# esenode.net
KiCad netlist of a schematic drawn in EAGLE
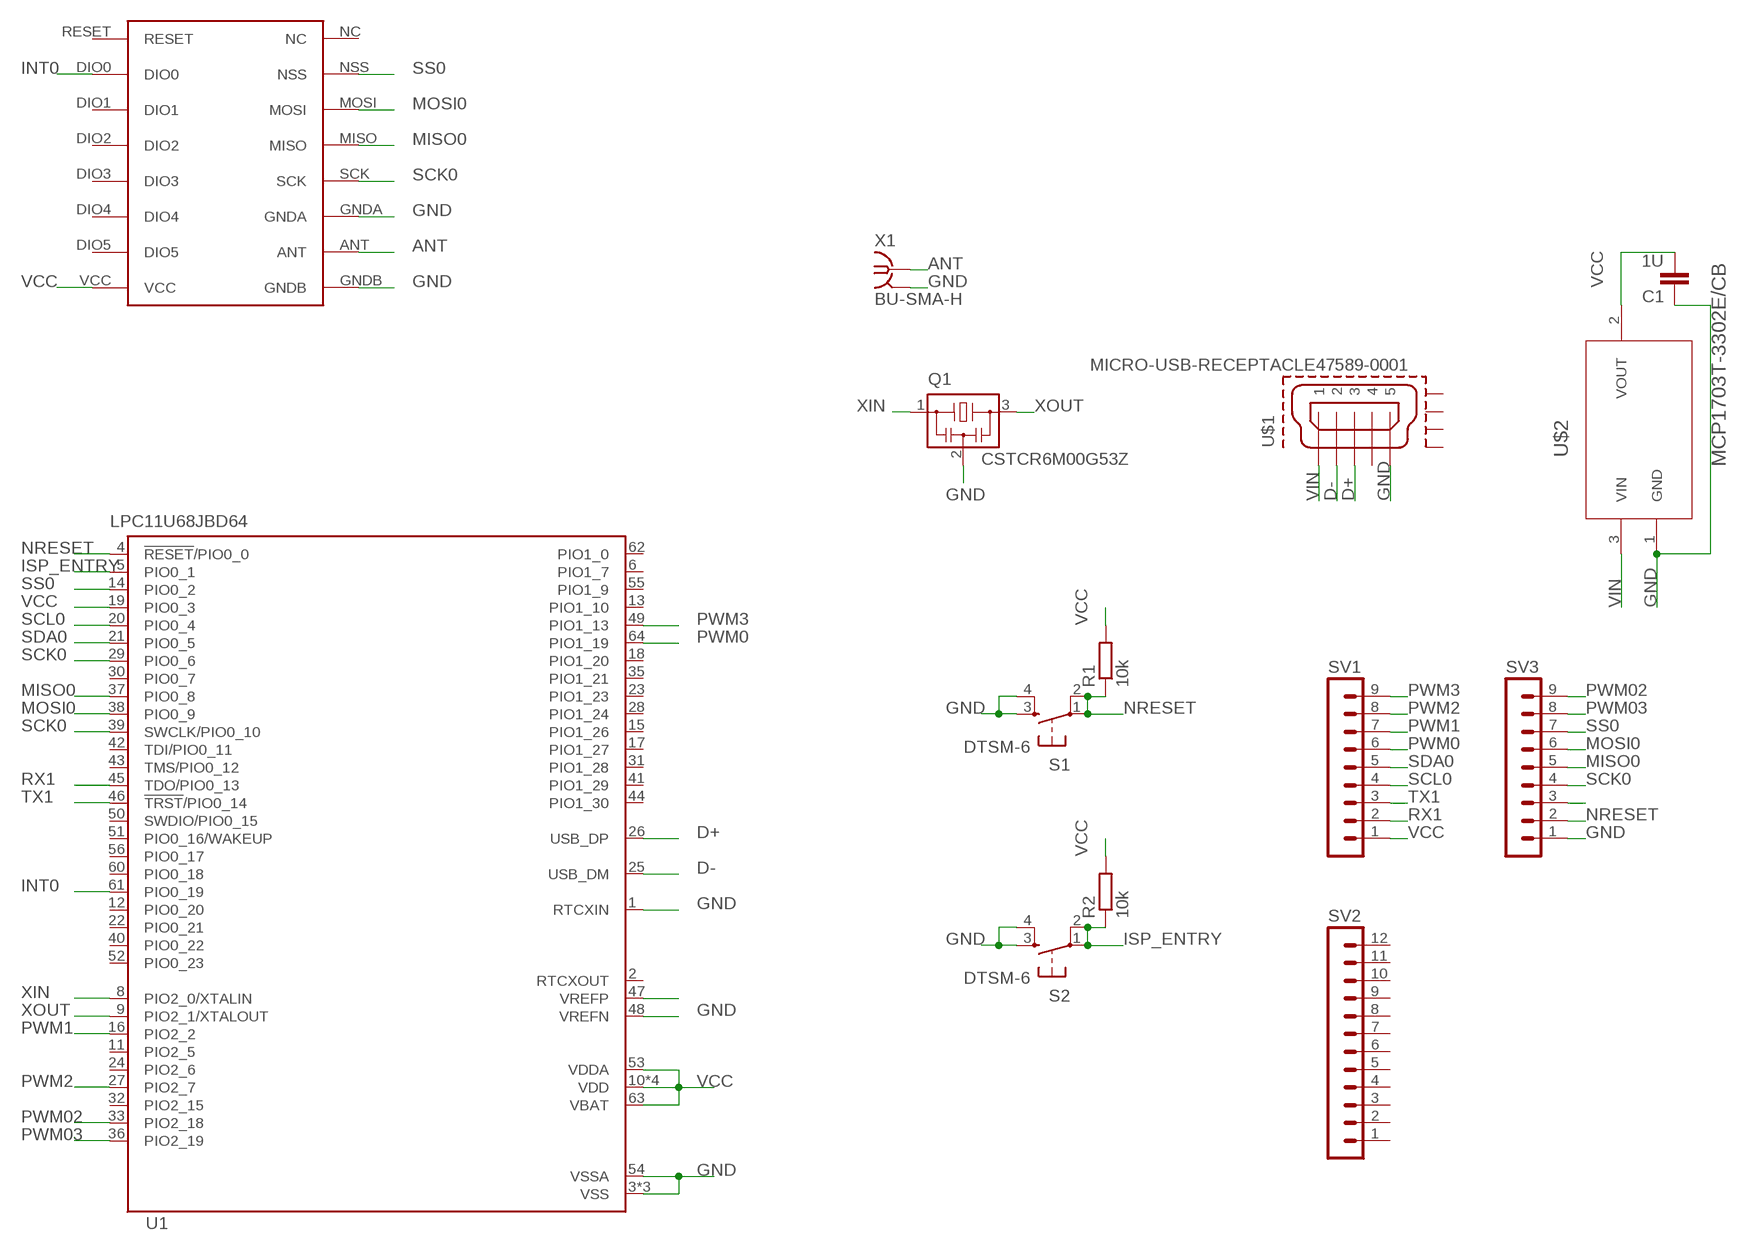
[diagram p0: schematic, sheet 1]

(export (version "E")
  (design (tool "Eeschema 10.0.6"))
  (components
    (comp (ref "C1")
      (value "1U")
      (footprint "eagle-import:C0805")
      (libsource (lib "eagle-import") (part "C-EUC0805"))
    )
    (comp (ref "Q1")
      (value "CSTCR6M00G53Z")
      (footprint "eagle-import:CSTCR6M")
      (fields (field (name "MPN") "CSTCR6M00G53-R0"))
      (libsource (lib "eagle-import") (part "CSTCR6M00G53Z"))
    )
    (comp (ref "R1")
      (value "10k")
      (footprint "eagle-import:M0805")
      (libsource (lib "eagle-import") (part "R-EU_M0805"))
    )
    (comp (ref "R2")
      (value "10k")
      (footprint "eagle-import:M0805")
      (libsource (lib "eagle-import") (part "R-EU_M0805"))
    )
    (comp (ref "S1")
      (value "DTSM-6")
      (footprint "eagle-import:DTSM-6")
      (libsource (lib "eagle-import") (part "DTSM-6"))
    )
    (comp (ref "S2")
      (value "DTSM-6")
      (footprint "eagle-import:DTSM-6")
      (libsource (lib "eagle-import") (part "DTSM-6"))
    )
    (comp (ref "SV1")
      (value "MA09-1")
      (footprint "eagle-import:MA09-1")
      (libsource (lib "eagle-import") (part "MA09-1"))
    )
    (comp (ref "SV2")
      (value "MA12-1")
      (footprint "eagle-import:MA12-1")
      (libsource (lib "eagle-import") (part "MA12-1"))
    )
    (comp (ref "SV3")
      (value "MA09-1")
      (footprint "eagle-import:MA09-1")
      (libsource (lib "eagle-import") (part "MA09-1"))
    )
    (comp (ref "U$1")
      (value "MICRO-USB-RECEPTACLE47589-0001")
      (footprint "eagle-import:47589-0001")
      (libsource (lib "eagle-import") (part "MICRO-USB-RECEPTACLE47589-0001"))
    )
    (comp (ref "U$2")
      (value "MCP1703T-3302E/CB")
      (footprint "eagle-import:SOT95P300X145-3N")
      (libsource (lib "eagle-import") (part "MCP1703T-3302E/CB"))
    )
    (comp (ref "U$3")
      (value "RFM69HW")
      (footprint "eagle-import:RFM")
      (libsource (lib "eagle-import") (part "RFM69HW"))
    )
    (comp (ref "U1")
      (value "LPC11U68JBD64")
      (footprint "eagle-import:SOT314-2")
      (libsource (lib "eagle-import") (part "LPC11U68JBD64"))
    )
    (comp (ref "X1")
      (value "BU-SMA-H")
      (footprint "eagle-import:BU-SMA-H")
      (libsource (lib "eagle-import") (part "BU-SMA-H"))
    )
  )
  (nets
    (net (code "1") (name "/ANT") (class "Default")
      (node (ref "U$3") (pin "ANT") (pinfunction "ANT_ANT") (pintype "bidirectional"))
      (node (ref "X1") (pin "1") (pinfunction "1_1") (pintype "passive"))
    )
    (net (code "2") (name "/D+") (class "Default")
      (node (ref "U$1") (pin "3") (pinfunction "3_3") (pintype "input"))
      (node (ref "U1") (pin "26") (pinfunction "USB_DP_26") (pintype "bidirectional"))
    )
    (net (code "3") (name "/D-") (class "Default")
      (node (ref "U$1") (pin "2") (pinfunction "2_2") (pintype "input"))
      (node (ref "U1") (pin "25") (pinfunction "USB_DM_25") (pintype "bidirectional"))
    )
    (net (code "4") (name "/GND") (class "Default")
      (node (ref "C1") (pin "1") (pinfunction "1_1") (pintype "passive"))
      (node (ref "Q1") (pin "2") (pinfunction "2_2") (pintype "passive"))
      (node (ref "S1") (pin "3") (pinfunction "3_3") (pintype "passive"))
      (node (ref "S1") (pin "4") (pinfunction "4_4") (pintype "passive"))
      (node (ref "S2") (pin "3") (pinfunction "3_3") (pintype "passive"))
      (node (ref "S2") (pin "4") (pinfunction "4_4") (pintype "passive"))
      (node (ref "SV3") (pin "1") (pinfunction "1_1") (pintype "passive"))
      (node (ref "U$1") (pin "5") (pinfunction "5_5") (pintype "input"))
      (node (ref "U$2") (pin "1") (pinfunction "GND_1") (pintype "passive"))
      (node (ref "U$3") (pin "GNDA") (pinfunction "GNDA_GNDA") (pintype "bidirectional"))
      (node (ref "U$3") (pin "GNDB") (pinfunction "GNDB_GNDB") (pintype "bidirectional"))
      (node (ref "U1") (pin "1") (pinfunction "RTCXIN_1") (pintype "bidirectional"))
      (node (ref "U1") (pin "3") (pinfunction "VSS_3") (pintype "bidirectional"))
      (node (ref "U1") (pin "48") (pinfunction "VREFN_48") (pintype "bidirectional"))
      (node (ref "U1") (pin "54") (pinfunction "VSSA_54") (pintype "bidirectional"))
      (node (ref "U1") (pin "57") (pinfunction "VSS_57") (pintype "bidirectional"))
      (node (ref "U1") (pin "7") (pinfunction "VSS_7") (pintype "bidirectional"))
      (node (ref "X1") (pin "2") (pinfunction "2_2") (pintype "passive"))
      (node (ref "X1") (pin "3") (pinfunction "2_3") (pintype "passive"))
      (node (ref "X1") (pin "4") (pinfunction "2_4") (pintype "passive"))
      (node (ref "X1") (pin "5") (pinfunction "2_5") (pintype "passive"))
    )
    (net (code "5") (name "/INT0") (class "Default")
      (node (ref "U$3") (pin "DIO0") (pinfunction "DIO0_DIO0") (pintype "bidirectional"))
      (node (ref "U1") (pin "61") (pinfunction "PIO0_19_61") (pintype "bidirectional"))
    )
    (net (code "6") (name "/ISP_ENTRY") (class "Default")
      (node (ref "R2") (pin "1") (pinfunction "1_1") (pintype "passive"))
      (node (ref "S2") (pin "1") (pinfunction "1_1") (pintype "passive"))
      (node (ref "S2") (pin "2") (pinfunction "2_2") (pintype "passive"))
      (node (ref "U1") (pin "5") (pinfunction "PIO0_1_5") (pintype "bidirectional"))
    )
    (net (code "7") (name "/MISO0") (class "Default")
      (node (ref "SV3") (pin "5") (pinfunction "5_5") (pintype "passive"))
      (node (ref "U$3") (pin "MISO") (pinfunction "MISO_MISO") (pintype "bidirectional"))
      (node (ref "U1") (pin "37") (pinfunction "PIO0_8_37") (pintype "bidirectional"))
    )
    (net (code "8") (name "/MOSI0") (class "Default")
      (node (ref "SV3") (pin "6") (pinfunction "6_6") (pintype "passive"))
      (node (ref "U$3") (pin "MOSI") (pinfunction "MOSI_MOSI") (pintype "bidirectional"))
      (node (ref "U1") (pin "38") (pinfunction "PIO0_9_38") (pintype "bidirectional"))
    )
    (net (code "9") (name "/NRESET") (class "Default")
      (node (ref "R1") (pin "1") (pinfunction "1_1") (pintype "passive"))
      (node (ref "S1") (pin "1") (pinfunction "1_1") (pintype "passive"))
      (node (ref "S1") (pin "2") (pinfunction "2_2") (pintype "passive"))
      (node (ref "SV3") (pin "2") (pinfunction "2_2") (pintype "passive"))
      (node (ref "U1") (pin "4") (pinfunction "~{RESET}/PIO0_0_4") (pintype "bidirectional"))
    )
    (net (code "10") (name "/PWM0") (class "Default")
      (node (ref "SV1") (pin "6") (pinfunction "6_6") (pintype "passive"))
      (node (ref "U1") (pin "64") (pinfunction "PIO1_19_64") (pintype "bidirectional"))
    )
    (net (code "11") (name "/PWM1") (class "Default")
      (node (ref "SV1") (pin "7") (pinfunction "7_7") (pintype "passive"))
      (node (ref "U1") (pin "16") (pinfunction "PIO2_2_16") (pintype "bidirectional"))
    )
    (net (code "12") (name "/PWM02") (class "Default")
      (node (ref "SV3") (pin "9") (pinfunction "9_9") (pintype "passive"))
      (node (ref "U1") (pin "33") (pinfunction "PIO2_18_33") (pintype "bidirectional"))
    )
    (net (code "13") (name "/PWM2") (class "Default")
      (node (ref "SV1") (pin "8") (pinfunction "8_8") (pintype "passive"))
      (node (ref "U1") (pin "27") (pinfunction "PIO2_7_27") (pintype "bidirectional"))
    )
    (net (code "14") (name "/PWM3") (class "Default")
      (node (ref "SV1") (pin "9") (pinfunction "9_9") (pintype "passive"))
      (node (ref "U1") (pin "49") (pinfunction "PIO1_13_49") (pintype "bidirectional"))
    )
    (net (code "15") (name "/PWM03") (class "Default")
      (node (ref "SV3") (pin "8") (pinfunction "8_8") (pintype "passive"))
      (node (ref "U1") (pin "36") (pinfunction "PIO2_19_36") (pintype "bidirectional"))
    )
    (net (code "16") (name "/RX1") (class "Default")
      (node (ref "SV1") (pin "2") (pinfunction "2_2") (pintype "passive"))
      (node (ref "U1") (pin "45") (pinfunction "TDO/PIO0_13_45") (pintype "bidirectional"))
    )
    (net (code "17") (name "/SCK0") (class "Default")
      (node (ref "SV3") (pin "4") (pinfunction "4_4") (pintype "passive"))
      (node (ref "U$3") (pin "SCK") (pinfunction "SCK_SCK") (pintype "bidirectional"))
      (node (ref "U1") (pin "29") (pinfunction "PIO0_6_29") (pintype "bidirectional"))
      (node (ref "U1") (pin "39") (pinfunction "SWCLK/PIO0_10_39") (pintype "bidirectional"))
    )
    (net (code "18") (name "/SCL0") (class "Default")
      (node (ref "SV1") (pin "4") (pinfunction "4_4") (pintype "passive"))
      (node (ref "U1") (pin "20") (pinfunction "PIO0_4_20") (pintype "bidirectional"))
    )
    (net (code "19") (name "/SDA0") (class "Default")
      (node (ref "SV1") (pin "5") (pinfunction "5_5") (pintype "passive"))
      (node (ref "U1") (pin "21") (pinfunction "PIO0_5_21") (pintype "bidirectional"))
    )
    (net (code "20") (name "/SS0") (class "Default")
      (node (ref "SV3") (pin "7") (pinfunction "7_7") (pintype "passive"))
      (node (ref "U$3") (pin "NSS") (pinfunction "NSS_NSS") (pintype "bidirectional"))
      (node (ref "U1") (pin "14") (pinfunction "PIO0_2_14") (pintype "bidirectional"))
    )
    (net (code "21") (name "/TX1") (class "Default")
      (node (ref "SV1") (pin "3") (pinfunction "3_3") (pintype "passive"))
      (node (ref "U1") (pin "46") (pinfunction "~{TRST}/PIO0_14_46") (pintype "bidirectional"))
    )
    (net (code "22") (name "/VCC") (class "Default")
      (node (ref "C1") (pin "2") (pinfunction "2_2") (pintype "passive"))
      (node (ref "R1") (pin "2") (pinfunction "2_2") (pintype "passive"))
      (node (ref "R2") (pin "2") (pinfunction "2_2") (pintype "passive"))
      (node (ref "SV1") (pin "1") (pinfunction "1_1") (pintype "passive"))
      (node (ref "U$2") (pin "2") (pinfunction "VOUT_2") (pintype "output"))
      (node (ref "U$3") (pin "VCC") (pinfunction "VCC_VCC") (pintype "bidirectional"))
      (node (ref "U1") (pin "10") (pinfunction "VDD_10") (pintype "bidirectional"))
      (node (ref "U1") (pin "19") (pinfunction "PIO0_3_19") (pintype "bidirectional"))
      (node (ref "U1") (pin "34") (pinfunction "VDD_34") (pintype "bidirectional"))
      (node (ref "U1") (pin "53") (pinfunction "VDDA_53") (pintype "bidirectional"))
      (node (ref "U1") (pin "58") (pinfunction "VDD_58") (pintype "bidirectional"))
      (node (ref "U1") (pin "59") (pinfunction "VDD_59") (pintype "bidirectional"))
      (node (ref "U1") (pin "63") (pinfunction "VBAT_63") (pintype "bidirectional"))
    )
    (net (code "23") (name "/VIN") (class "Default")
      (node (ref "U$1") (pin "1") (pinfunction "1_1") (pintype "input"))
      (node (ref "U$2") (pin "3") (pinfunction "VIN_3") (pintype "input"))
    )
    (net (code "24") (name "/XIN") (class "Default")
      (node (ref "Q1") (pin "1") (pinfunction "1_1") (pintype "passive"))
      (node (ref "U1") (pin "8") (pinfunction "PIO2_0/XTALIN_8") (pintype "bidirectional"))
    )
    (net (code "25") (name "/XOUT") (class "Default")
      (node (ref "Q1") (pin "3") (pinfunction "3_3") (pintype "passive"))
      (node (ref "U1") (pin "9") (pinfunction "PIO2_1/XTALOUT_9") (pintype "bidirectional"))
    )
    (net (code "26") (name "unconnected-(SV2-Pad1)") (class "Default")
      (node (ref "SV2") (pin "1") (pinfunction "1_1") (pintype "passive"))
    )
    (net (code "27") (name "unconnected-(SV2-Pad2)") (class "Default")
      (node (ref "SV2") (pin "2") (pinfunction "2_2") (pintype "passive"))
    )
    (net (code "28") (name "unconnected-(SV2-Pad3)") (class "Default")
      (node (ref "SV2") (pin "3") (pinfunction "3_3") (pintype "passive"))
    )
    (net (code "29") (name "unconnected-(SV2-Pad4)") (class "Default")
      (node (ref "SV2") (pin "4") (pinfunction "4_4") (pintype "passive"))
    )
    (net (code "30") (name "unconnected-(SV2-Pad5)") (class "Default")
      (node (ref "SV2") (pin "5") (pinfunction "5_5") (pintype "passive"))
    )
    (net (code "31") (name "unconnected-(SV2-Pad6)") (class "Default")
      (node (ref "SV2") (pin "6") (pinfunction "6_6") (pintype "passive"))
    )
    (net (code "32") (name "unconnected-(SV2-Pad7)") (class "Default")
      (node (ref "SV2") (pin "7") (pinfunction "7_7") (pintype "passive"))
    )
    (net (code "33") (name "unconnected-(SV2-Pad8)") (class "Default")
      (node (ref "SV2") (pin "8") (pinfunction "8_8") (pintype "passive"))
    )
    (net (code "34") (name "unconnected-(SV2-Pad9)") (class "Default")
      (node (ref "SV2") (pin "9") (pinfunction "9_9") (pintype "passive"))
    )
    (net (code "35") (name "unconnected-(SV2-Pad10)") (class "Default")
      (node (ref "SV2") (pin "10") (pinfunction "10_10") (pintype "passive"))
    )
    (net (code "36") (name "unconnected-(SV2-Pad11)") (class "Default")
      (node (ref "SV2") (pin "11") (pinfunction "11_11") (pintype "passive"))
    )
    (net (code "37") (name "unconnected-(SV2-Pad12)") (class "Default")
      (node (ref "SV2") (pin "12") (pinfunction "12_12") (pintype "passive"))
    )
    (net (code "38") (name "unconnected-(SV3-Pad3)") (class "Default")
      (node (ref "SV3") (pin "3") (pinfunction "3_3") (pintype "passive"))
    )
    (net (code "39") (name "unconnected-(U$1-GND1-PadCASING1)") (class "Default")
      (node (ref "U$1") (pin "CASING1") (pinfunction "GND1_CASING1") (pintype "bidirectional"))
    )
    (net (code "40") (name "unconnected-(U$1-GND2-PadCASING2)") (class "Default")
      (node (ref "U$1") (pin "CASING2") (pinfunction "GND2_CASING2") (pintype "bidirectional"))
    )
    (net (code "41") (name "unconnected-(U$1-GND3-PadCASING3)") (class "Default")
      (node (ref "U$1") (pin "CASING3") (pinfunction "GND3_CASING3") (pintype "bidirectional"))
    )
    (net (code "42") (name "unconnected-(U$1-GND4-PadCASING4)") (class "Default")
      (node (ref "U$1") (pin "CASING4") (pinfunction "GND4_CASING4") (pintype "bidirectional"))
    )
    (net (code "43") (name "unconnected-(U$1-Pad4)") (class "Default")
      (node (ref "U$1") (pin "4") (pinfunction "4_4") (pintype "input"))
    )
    (net (code "44") (name "unconnected-(U$3-PadDIO1)") (class "Default")
      (node (ref "U$3") (pin "DIO1") (pinfunction "DIO1_DIO1") (pintype "bidirectional"))
    )
    (net (code "45") (name "unconnected-(U$3-PadDIO2)") (class "Default")
      (node (ref "U$3") (pin "DIO2") (pinfunction "DIO2_DIO2") (pintype "bidirectional"))
    )
    (net (code "46") (name "unconnected-(U$3-PadDIO3)") (class "Default")
      (node (ref "U$3") (pin "DIO3") (pinfunction "DIO3_DIO3") (pintype "bidirectional"))
    )
    (net (code "47") (name "unconnected-(U$3-PadDIO4)") (class "Default")
      (node (ref "U$3") (pin "DIO4") (pinfunction "DIO4_DIO4") (pintype "bidirectional"))
    )
    (net (code "48") (name "unconnected-(U$3-PadDIO5)") (class "Default")
      (node (ref "U$3") (pin "DIO5") (pinfunction "DIO5_DIO5") (pintype "bidirectional"))
    )
    (net (code "49") (name "unconnected-(U$3-PadNC)") (class "Default")
      (node (ref "U$3") (pin "NC") (pinfunction "NC_NC") (pintype "bidirectional"))
    )
    (net (code "50") (name "unconnected-(U$3-PadRESET)") (class "Default")
      (node (ref "U$3") (pin "RESET") (pinfunction "RESET_RESET") (pintype "bidirectional"))
    )
    (net (code "51") (name "unconnected-(U1-PIO0_7-Pad30)") (class "Default")
      (node (ref "U1") (pin "30") (pinfunction "PIO0_7_30") (pintype "bidirectional"))
    )
    (net (code "52") (name "unconnected-(U1-PIO0_16{slash}WAKEUP-Pad51)") (class "Default")
      (node (ref "U1") (pin "51") (pinfunction "PIO0_16/WAKEUP_51") (pintype "bidirectional"))
    )
    (net (code "53") (name "unconnected-(U1-PIO0_17-Pad56)") (class "Default")
      (node (ref "U1") (pin "56") (pinfunction "PIO0_17_56") (pintype "bidirectional"))
    )
    (net (code "54") (name "unconnected-(U1-PIO0_18-Pad60)") (class "Default")
      (node (ref "U1") (pin "60") (pinfunction "PIO0_18_60") (pintype "bidirectional"))
    )
    (net (code "55") (name "unconnected-(U1-PIO0_20-Pad12)") (class "Default")
      (node (ref "U1") (pin "12") (pinfunction "PIO0_20_12") (pintype "bidirectional"))
    )
    (net (code "56") (name "unconnected-(U1-PIO0_21-Pad22)") (class "Default")
      (node (ref "U1") (pin "22") (pinfunction "PIO0_21_22") (pintype "bidirectional"))
    )
    (net (code "57") (name "unconnected-(U1-PIO0_22-Pad40)") (class "Default")
      (node (ref "U1") (pin "40") (pinfunction "PIO0_22_40") (pintype "bidirectional"))
    )
    (net (code "58") (name "unconnected-(U1-PIO0_23-Pad52)") (class "Default")
      (node (ref "U1") (pin "52") (pinfunction "PIO0_23_52") (pintype "bidirectional"))
    )
    (net (code "59") (name "unconnected-(U1-PIO1_0-Pad62)") (class "Default")
      (node (ref "U1") (pin "62") (pinfunction "PIO1_0_62") (pintype "bidirectional"))
    )
    (net (code "60") (name "unconnected-(U1-PIO1_7-Pad6)") (class "Default")
      (node (ref "U1") (pin "6") (pinfunction "PIO1_7_6") (pintype "bidirectional"))
    )
    (net (code "61") (name "unconnected-(U1-PIO1_9-Pad55)") (class "Default")
      (node (ref "U1") (pin "55") (pinfunction "PIO1_9_55") (pintype "bidirectional"))
    )
    (net (code "62") (name "unconnected-(U1-PIO1_10-Pad13)") (class "Default")
      (node (ref "U1") (pin "13") (pinfunction "PIO1_10_13") (pintype "bidirectional"))
    )
    (net (code "63") (name "unconnected-(U1-PIO1_20-Pad18)") (class "Default")
      (node (ref "U1") (pin "18") (pinfunction "PIO1_20_18") (pintype "bidirectional"))
    )
    (net (code "64") (name "unconnected-(U1-PIO1_21-Pad35)") (class "Default")
      (node (ref "U1") (pin "35") (pinfunction "PIO1_21_35") (pintype "bidirectional"))
    )
    (net (code "65") (name "unconnected-(U1-PIO1_23-Pad23)") (class "Default")
      (node (ref "U1") (pin "23") (pinfunction "PIO1_23_23") (pintype "bidirectional"))
    )
    (net (code "66") (name "unconnected-(U1-PIO1_24-Pad28)") (class "Default")
      (node (ref "U1") (pin "28") (pinfunction "PIO1_24_28") (pintype "bidirectional"))
    )
    (net (code "67") (name "unconnected-(U1-PIO1_26-Pad15)") (class "Default")
      (node (ref "U1") (pin "15") (pinfunction "PIO1_26_15") (pintype "bidirectional"))
    )
    (net (code "68") (name "unconnected-(U1-PIO1_27-Pad17)") (class "Default")
      (node (ref "U1") (pin "17") (pinfunction "PIO1_27_17") (pintype "bidirectional"))
    )
    (net (code "69") (name "unconnected-(U1-PIO1_28-Pad31)") (class "Default")
      (node (ref "U1") (pin "31") (pinfunction "PIO1_28_31") (pintype "bidirectional"))
    )
    (net (code "70") (name "unconnected-(U1-PIO1_29-Pad41)") (class "Default")
      (node (ref "U1") (pin "41") (pinfunction "PIO1_29_41") (pintype "bidirectional"))
    )
    (net (code "71") (name "unconnected-(U1-PIO1_30-Pad44)") (class "Default")
      (node (ref "U1") (pin "44") (pinfunction "PIO1_30_44") (pintype "bidirectional"))
    )
    (net (code "72") (name "unconnected-(U1-PIO2_5-Pad11)") (class "Default")
      (node (ref "U1") (pin "11") (pinfunction "PIO2_5_11") (pintype "bidirectional"))
    )
    (net (code "73") (name "unconnected-(U1-PIO2_6-Pad24)") (class "Default")
      (node (ref "U1") (pin "24") (pinfunction "PIO2_6_24") (pintype "bidirectional"))
    )
    (net (code "74") (name "unconnected-(U1-PIO2_15-Pad32)") (class "Default")
      (node (ref "U1") (pin "32") (pinfunction "PIO2_15_32") (pintype "bidirectional"))
    )
    (net (code "75") (name "unconnected-(U1-RTCXOUT-Pad2)") (class "Default")
      (node (ref "U1") (pin "2") (pinfunction "RTCXOUT_2") (pintype "bidirectional"))
    )
    (net (code "76") (name "unconnected-(U1-SWDIO{slash}PIO0_15-Pad50)") (class "Default")
      (node (ref "U1") (pin "50") (pinfunction "SWDIO/PIO0_15_50") (pintype "bidirectional"))
    )
    (net (code "77") (name "unconnected-(U1-TDI{slash}PIO0_11-Pad42)") (class "Default")
      (node (ref "U1") (pin "42") (pinfunction "TDI/PIO0_11_42") (pintype "bidirectional"))
    )
    (net (code "78") (name "unconnected-(U1-TMS{slash}PIO0_12-Pad43)") (class "Default")
      (node (ref "U1") (pin "43") (pinfunction "TMS/PIO0_12_43") (pintype "bidirectional"))
    )
    (net (code "79") (name "unconnected-(U1-VREFP-Pad47)") (class "Default")
      (node (ref "U1") (pin "47") (pinfunction "VREFP_47") (pintype "bidirectional"))
    )
  )
)
